# tinyduino-breakout-mk-4_1.net
KiCad netlist of a schematic drawn in EAGLE
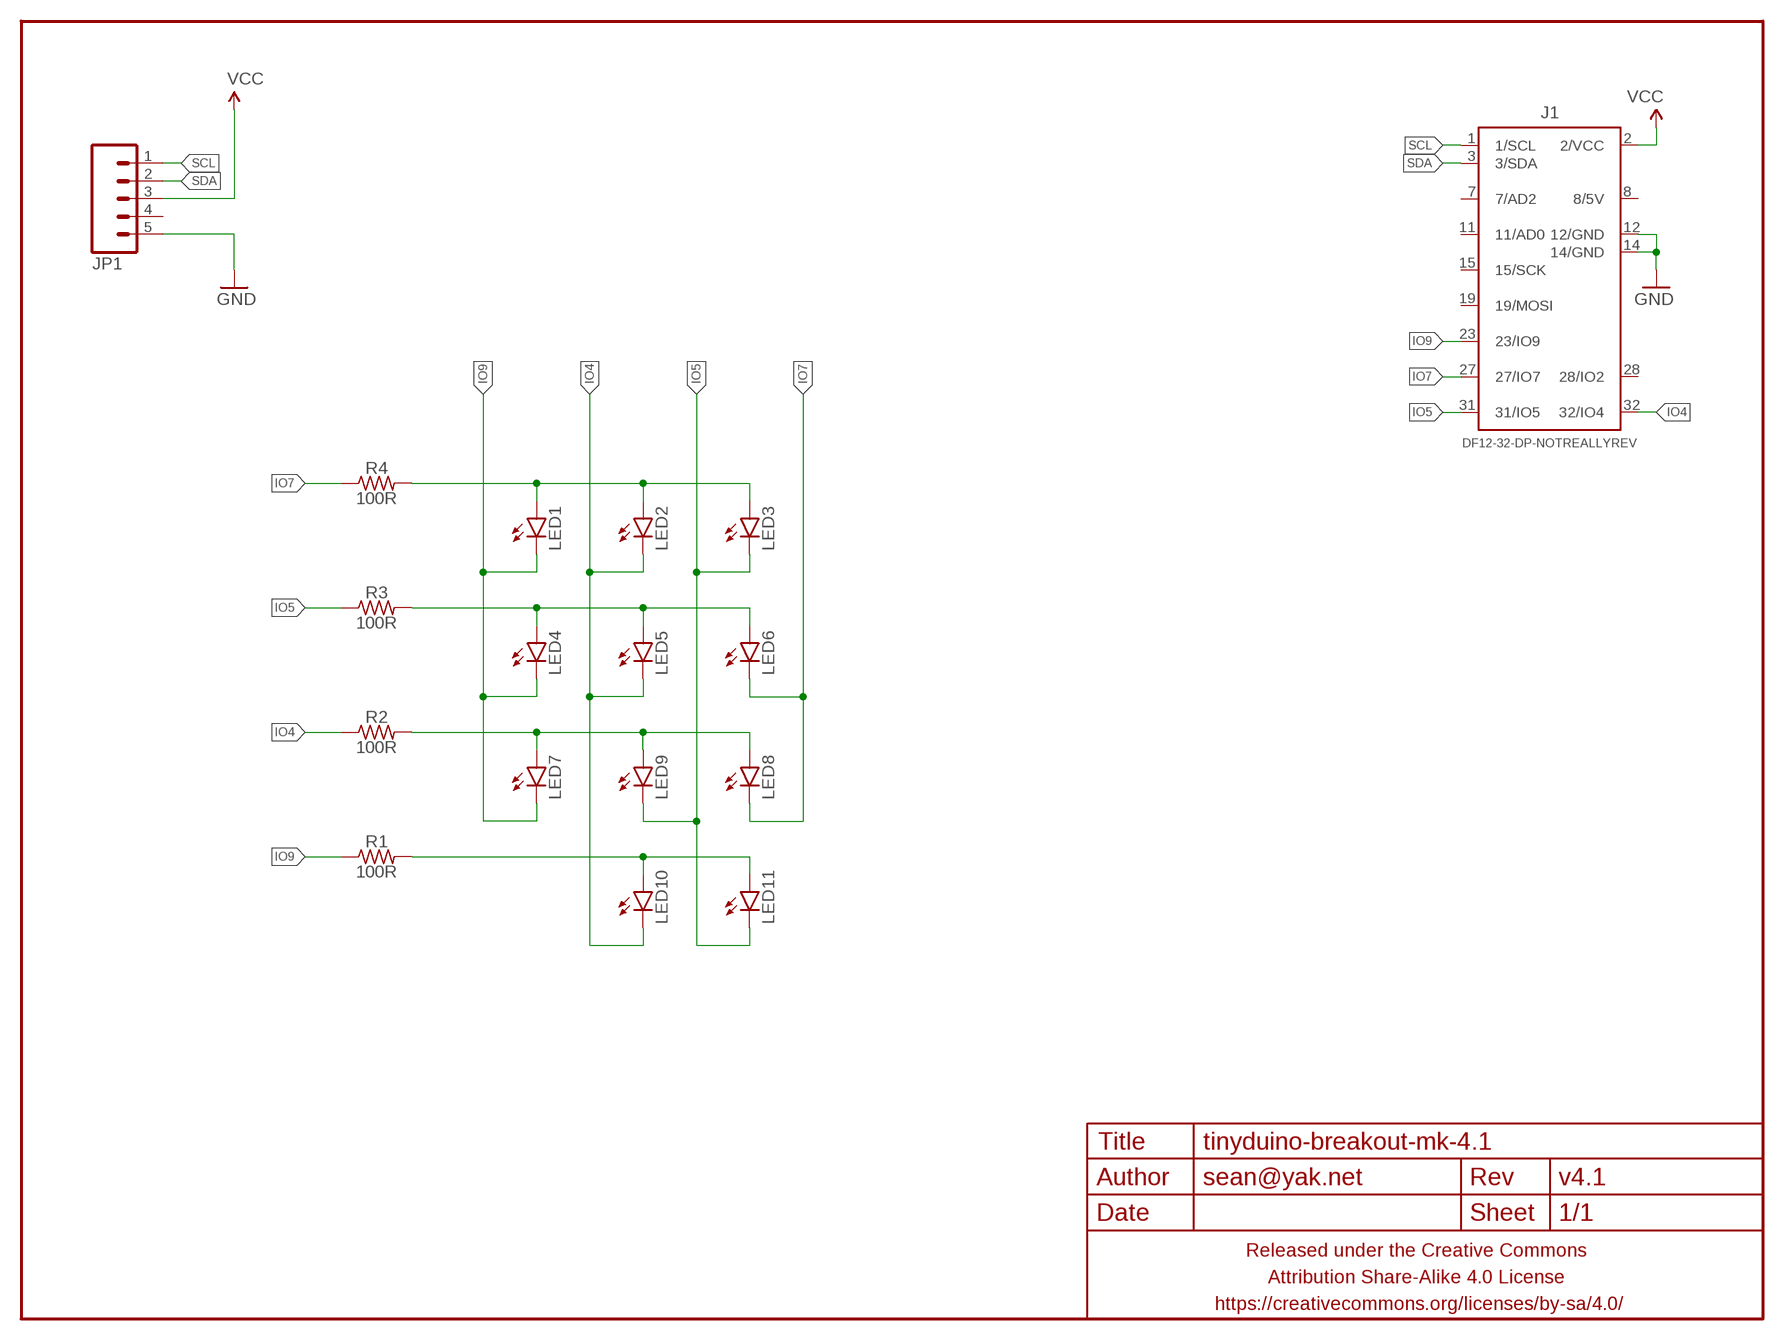
[diagram p0: schematic, sheet 1]

(export (version "E")
  (design (tool "Eeschema 10.0.6"))
  (components
    (comp (ref "FRAME1")
      (value "FRAME-LETTERNO_PACKAGE")
      (footprint "eagle-import:DUMMY")
      (fields (field (name "DESIGNER") "sean@yak.net") (field (name "VERSION") "v4.1"))
      (libsource (lib "eagle-import") (part "FRAME-LETTERNO_PACKAGE"))
    )
    (comp (ref "J1")
      (value "DF12-32-DP-NOTREALLYREV")
      (footprint "eagle-import:DF12-32-DP-I2C+EXTRA-REV")
      (libsource (lib "eagle-import") (part "DF12-32-DP-NOTREALLYREV"))
    )
    (comp (ref "JP1")
      (value "M05SMD-SHORT")
      (footprint "eagle-import:1X05-SMD-SHORT")
      (libsource (lib "eagle-import") (part "M05SMD-SHORT"))
    )
    (comp (ref "LED1")
      (value "LED0603")
      (footprint "eagle-import:LED-0603")
      (libsource (lib "eagle-import") (part "LED0603"))
    )
    (comp (ref "LED2")
      (value "LED0603")
      (footprint "eagle-import:LED-0603")
      (libsource (lib "eagle-import") (part "LED0603"))
    )
    (comp (ref "LED3")
      (value "LED0603")
      (footprint "eagle-import:LED-0603")
      (libsource (lib "eagle-import") (part "LED0603"))
    )
    (comp (ref "LED4")
      (value "LED0603")
      (footprint "eagle-import:LED-0603")
      (libsource (lib "eagle-import") (part "LED0603"))
    )
    (comp (ref "LED5")
      (value "LED0603")
      (footprint "eagle-import:LED-0603")
      (libsource (lib "eagle-import") (part "LED0603"))
    )
    (comp (ref "LED6")
      (value "LED0603")
      (footprint "eagle-import:LED-0603")
      (libsource (lib "eagle-import") (part "LED0603"))
    )
    (comp (ref "LED7")
      (value "LED0603")
      (footprint "eagle-import:LED-0603")
      (libsource (lib "eagle-import") (part "LED0603"))
    )
    (comp (ref "LED8")
      (value "LED0603")
      (footprint "eagle-import:LED-0603")
      (libsource (lib "eagle-import") (part "LED0603"))
    )
    (comp (ref "LED9")
      (value "LED0603")
      (footprint "eagle-import:LED-0603")
      (libsource (lib "eagle-import") (part "LED0603"))
    )
    (comp (ref "LED10")
      (value "LED0603")
      (footprint "eagle-import:LED-0603")
      (libsource (lib "eagle-import") (part "LED0603"))
    )
    (comp (ref "LED11")
      (value "LED0603")
      (footprint "eagle-import:LED-0603")
      (libsource (lib "eagle-import") (part "LED0603"))
    )
    (comp (ref "R1")
      (value "100R")
      (footprint "eagle-import:R0603")
      (libsource (lib "eagle-import") (part "RESISTORR0603"))
    )
    (comp (ref "R2")
      (value "100R")
      (footprint "eagle-import:R0603")
      (libsource (lib "eagle-import") (part "RESISTORR0603"))
    )
    (comp (ref "R3")
      (value "100R")
      (footprint "eagle-import:R0603")
      (libsource (lib "eagle-import") (part "RESISTORR0603"))
    )
    (comp (ref "R4")
      (value "100R")
      (footprint "eagle-import:R0603")
      (libsource (lib "eagle-import") (part "RESISTORR0603"))
    )
  )
  (nets
    (net (code "1") (name "GND") (class "Default")
      (node (ref "J1") (pin "12") (pinfunction "12/GND_12") (pintype "bidirectional"))
      (node (ref "J1") (pin "14") (pinfunction "14/GND_14") (pintype "bidirectional"))
      (node (ref "JP1") (pin "5") (pinfunction "5_5") (pintype "passive"))
    )
    (net (code "2") (name "IO4") (class "Default")
      (node (ref "J1") (pin "32") (pinfunction "32/IO4_32") (pintype "bidirectional"))
      (node (ref "LED10") (pin "C") (pinfunction "C_C") (pintype "passive"))
      (node (ref "LED2") (pin "C") (pinfunction "C_C") (pintype "passive"))
      (node (ref "LED5") (pin "C") (pinfunction "C_C") (pintype "passive"))
      (node (ref "R2") (pin "1") (pinfunction "1_1") (pintype "passive"))
    )
    (net (code "3") (name "IO5") (class "Default")
      (node (ref "J1") (pin "31") (pinfunction "31/IO5_31") (pintype "bidirectional"))
      (node (ref "LED11") (pin "C") (pinfunction "C_C") (pintype "passive"))
      (node (ref "LED3") (pin "C") (pinfunction "C_C") (pintype "passive"))
      (node (ref "LED9") (pin "C") (pinfunction "C_C") (pintype "passive"))
      (node (ref "R3") (pin "1") (pinfunction "1_1") (pintype "passive"))
    )
    (net (code "4") (name "IO7") (class "Default")
      (node (ref "J1") (pin "27") (pinfunction "27/IO7_27") (pintype "bidirectional"))
      (node (ref "LED6") (pin "C") (pinfunction "C_C") (pintype "passive"))
      (node (ref "LED8") (pin "C") (pinfunction "C_C") (pintype "passive"))
      (node (ref "R4") (pin "1") (pinfunction "1_1") (pintype "passive"))
    )
    (net (code "5") (name "IO9") (class "Default")
      (node (ref "J1") (pin "23") (pinfunction "23/IO9_23") (pintype "bidirectional"))
      (node (ref "LED1") (pin "C") (pinfunction "C_C") (pintype "passive"))
      (node (ref "LED4") (pin "C") (pinfunction "C_C") (pintype "passive"))
      (node (ref "LED7") (pin "C") (pinfunction "C_C") (pintype "passive"))
      (node (ref "R1") (pin "1") (pinfunction "1_1") (pintype "passive"))
    )
    (net (code "6") (name "Net-(LED1-PadA)") (class "Default")
      (node (ref "LED1") (pin "A") (pinfunction "A_A") (pintype "passive"))
      (node (ref "LED2") (pin "A") (pinfunction "A_A") (pintype "passive"))
      (node (ref "LED3") (pin "A") (pinfunction "A_A") (pintype "passive"))
      (node (ref "R4") (pin "2") (pinfunction "2_2") (pintype "passive"))
    )
    (net (code "7") (name "Net-(LED4-PadA)") (class "Default")
      (node (ref "LED4") (pin "A") (pinfunction "A_A") (pintype "passive"))
      (node (ref "LED5") (pin "A") (pinfunction "A_A") (pintype "passive"))
      (node (ref "LED6") (pin "A") (pinfunction "A_A") (pintype "passive"))
      (node (ref "R3") (pin "2") (pinfunction "2_2") (pintype "passive"))
    )
    (net (code "8") (name "Net-(LED7-PadA)") (class "Default")
      (node (ref "LED7") (pin "A") (pinfunction "A_A") (pintype "passive"))
      (node (ref "LED8") (pin "A") (pinfunction "A_A") (pintype "passive"))
      (node (ref "LED9") (pin "A") (pinfunction "A_A") (pintype "passive"))
      (node (ref "R2") (pin "2") (pinfunction "2_2") (pintype "passive"))
    )
    (net (code "9") (name "Net-(LED10-PadA)") (class "Default")
      (node (ref "LED10") (pin "A") (pinfunction "A_A") (pintype "passive"))
      (node (ref "LED11") (pin "A") (pinfunction "A_A") (pintype "passive"))
      (node (ref "R1") (pin "2") (pinfunction "2_2") (pintype "passive"))
    )
    (net (code "10") (name "SCL") (class "Default")
      (node (ref "J1") (pin "1") (pinfunction "1/SCL_1") (pintype "bidirectional"))
      (node (ref "JP1") (pin "1") (pinfunction "1_1") (pintype "passive"))
    )
    (net (code "11") (name "SDA") (class "Default")
      (node (ref "J1") (pin "3") (pinfunction "3/SDA_3") (pintype "bidirectional"))
      (node (ref "JP1") (pin "2") (pinfunction "2_2") (pintype "passive"))
    )
    (net (code "12") (name "VCC") (class "Default")
      (node (ref "J1") (pin "2") (pinfunction "2/VCC_2") (pintype "bidirectional"))
      (node (ref "JP1") (pin "3") (pinfunction "3_3") (pintype "passive"))
    )
    (net (code "13") (name "unconnected-(J1-7{slash}AD2-Pad7)") (class "Default")
      (node (ref "J1") (pin "7") (pinfunction "7/AD2_7") (pintype "bidirectional"))
    )
    (net (code "14") (name "unconnected-(J1-8{slash}5V-Pad8)") (class "Default")
      (node (ref "J1") (pin "8") (pinfunction "8/5V_8") (pintype "bidirectional"))
    )
    (net (code "15") (name "unconnected-(J1-11{slash}AD0-Pad11)") (class "Default")
      (node (ref "J1") (pin "11") (pinfunction "11/AD0_11") (pintype "bidirectional"))
    )
    (net (code "16") (name "unconnected-(J1-15{slash}SCK-Pad15)") (class "Default")
      (node (ref "J1") (pin "15") (pinfunction "15/SCK_15") (pintype "bidirectional"))
    )
    (net (code "17") (name "unconnected-(J1-19{slash}MOSI-Pad19)") (class "Default")
      (node (ref "J1") (pin "19") (pinfunction "19/MOSI_19") (pintype "bidirectional"))
    )
    (net (code "18") (name "unconnected-(J1-28{slash}IO2-Pad28)") (class "Default")
      (node (ref "J1") (pin "28") (pinfunction "28/IO2_28") (pintype "bidirectional"))
    )
    (net (code "19") (name "unconnected-(JP1-Pad4)") (class "Default")
      (node (ref "JP1") (pin "4") (pinfunction "4_4") (pintype "passive"))
    )
  )
)
